# ESC.net
KiCad netlist of a schematic drawn in Altium Designer
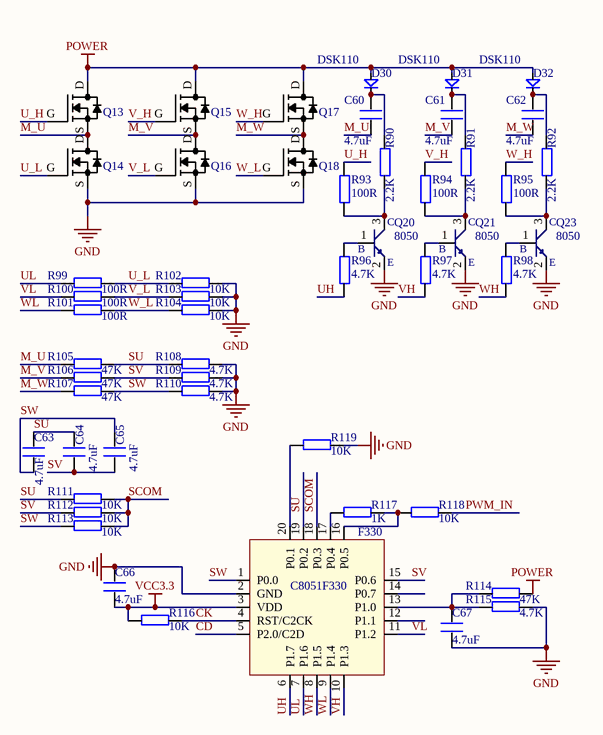
[diagram p0: ESC.SchDoc]

(export (version "E")
  (design (tool "Eeschema 10.0.6"))
  (components
    (comp (ref "C60")
      (value "4.7uF")
      (footprint "C 0603_L")
      (libsource (lib "WarShip V3 STM32103封装库") (part "C"))
    )
    (comp (ref "C61")
      (value "4.7uF")
      (footprint "C 0603_L")
      (libsource (lib "WarShip V3 STM32103封装库") (part "C"))
    )
    (comp (ref "C62")
      (value "4.7uF")
      (footprint "C 0603_L")
      (libsource (lib "WarShip V3 STM32103封装库") (part "C"))
    )
    (comp (ref "C63")
      (value "4.7uF")
      (footprint "C 0603_L")
      (libsource (lib "WarShip V3 STM32103封装库") (part "C"))
    )
    (comp (ref "C64")
      (value "4.7uF")
      (footprint "C 0603_L")
      (libsource (lib "WarShip V3 STM32103封装库") (part "C"))
    )
    (comp (ref "C65")
      (value "4.7uF")
      (footprint "C 0603_L")
      (libsource (lib "WarShip V3 STM32103封装库") (part "C"))
    )
    (comp (ref "C66")
      (value "4.7uF")
      (footprint "C 0603_L")
      (libsource (lib "WarShip V3 STM32103封装库") (part "C"))
    )
    (comp (ref "C67")
      (value "4.7uF")
      (footprint "C 0603_L")
      (libsource (lib "WarShip V3 STM32103封装库") (part "C"))
    )
    (comp (ref "D30")
      (value "DSK110")
      (footprint "SOD-123F")
      (description "通用二极管 100V-1A")
      (fields (field (name "版权归属") "源创客"))
      (libsource (lib "二极管-整流桥") (part "DSK110"))
    )
    (comp (ref "D31")
      (value "DSK110")
      (footprint "SOD-123F")
      (description "通用二极管 100V-1A")
      (fields (field (name "版权归属") "源创客"))
      (libsource (lib "二极管-整流桥") (part "DSK110"))
    )
    (comp (ref "D32")
      (value "DSK110")
      (footprint "SOD-123F")
      (description "通用二极管 100V-1A")
      (fields (field (name "版权归属") "源创客"))
      (libsource (lib "二极管-整流桥") (part "DSK110"))
    )
    (comp (ref "F330")
      (value "C8051F330")
      (footprint "QFN20_4*4_L")
      (description "C8051F330单片机")
      (libsource (lib "LovelessingSch") (part "C8051F330"))
    )
    (comp (ref "Q13")
      (value "NTMFS5C628NLT")
      (footprint "SO_8FL_DFN5")
      (description "MOSFET N-CH 60V SO8FL")
      (fields
        (field (name "MANUFACTURER") "ON Semiconductor")
        (field (name "MANUFACTURER PART NUMBER") "NTMFS5C628NLT1G")
      )
      (libsource (lib "MINIBLDC") (part "NTMFS5C628NLT"))
    )
    (comp (ref "Q14")
      (value "NTMFS5C628NLT")
      (footprint "SO_8FL_DFN5")
      (description "MOSFET N-CH 60V SO8FL")
      (fields
        (field (name "MANUFACTURER") "ON Semiconductor")
        (field (name "MANUFACTURER PART NUMBER") "NTMFS5C628NLT1G")
      )
      (libsource (lib "MINIBLDC") (part "NTMFS5C628NLT"))
    )
    (comp (ref "Q15")
      (value "NTMFS5C628NLT")
      (footprint "SO_8FL_DFN5")
      (description "MOSFET N-CH 60V SO8FL")
      (fields
        (field (name "MANUFACTURER") "ON Semiconductor")
        (field (name "MANUFACTURER PART NUMBER") "NTMFS5C628NLT1G")
      )
      (libsource (lib "MINIBLDC") (part "NTMFS5C628NLT"))
    )
    (comp (ref "Q16")
      (value "NTMFS5C628NLT")
      (footprint "SO_8FL_DFN5")
      (description "MOSFET N-CH 60V SO8FL")
      (fields
        (field (name "MANUFACTURER") "ON Semiconductor")
        (field (name "MANUFACTURER PART NUMBER") "NTMFS5C628NLT1G")
      )
      (libsource (lib "MINIBLDC") (part "NTMFS5C628NLT"))
    )
    (comp (ref "Q17")
      (value "NTMFS5C628NLT")
      (footprint "SO_8FL_DFN5")
      (description "MOSFET N-CH 60V SO8FL")
      (fields
        (field (name "MANUFACTURER") "ON Semiconductor")
        (field (name "MANUFACTURER PART NUMBER") "NTMFS5C628NLT1G")
      )
      (libsource (lib "MINIBLDC") (part "NTMFS5C628NLT"))
    )
    (comp (ref "Q18")
      (value "NTMFS5C628NLT")
      (footprint "SO_8FL_DFN5")
      (description "MOSFET N-CH 60V SO8FL")
      (fields
        (field (name "MANUFACTURER") "ON Semiconductor")
        (field (name "MANUFACTURER PART NUMBER") "NTMFS5C628NLT1G")
      )
      (libsource (lib "MINIBLDC") (part "NTMFS5C628NLT"))
    )
    (comp (ref "Q20")
      (value "8050")
      (footprint "SOT23-3L")
      (libsource (lib "LovelessingSch") (part "8050NPN"))
    )
    (comp (ref "Q21")
      (value "8050")
      (footprint "SOT23-3L")
      (libsource (lib "LovelessingSch") (part "8050NPN"))
    )
    (comp (ref "Q23")
      (value "8050")
      (footprint "SOT23-3L")
      (libsource (lib "LovelessingSch") (part "8050NPN"))
    )
    (comp (ref "R90")
      (value "2.2K")
      (footprint "R 0603_L")
      (libsource (lib "WarShip V3 STM32103封装库") (part "R"))
    )
    (comp (ref "R91")
      (value "2.2K")
      (footprint "R 0603_L")
      (libsource (lib "WarShip V3 STM32103封装库") (part "R"))
    )
    (comp (ref "R92")
      (value "2.2K")
      (footprint "R 0603_L")
      (libsource (lib "WarShip V3 STM32103封装库") (part "R"))
    )
    (comp (ref "R93")
      (value "100R")
      (footprint "R 0603_L")
      (libsource (lib "WarShip V3 STM32103封装库") (part "R"))
    )
    (comp (ref "R94")
      (value "100R")
      (footprint "R 0603_L")
      (libsource (lib "WarShip V3 STM32103封装库") (part "R"))
    )
    (comp (ref "R95")
      (value "100R")
      (footprint "R 0603_L")
      (libsource (lib "WarShip V3 STM32103封装库") (part "R"))
    )
    (comp (ref "R96")
      (value "4.7K")
      (footprint "R 0603_L")
      (libsource (lib "WarShip V3 STM32103封装库") (part "R"))
    )
    (comp (ref "R97")
      (value "4.7K")
      (footprint "R 0603_L")
      (libsource (lib "WarShip V3 STM32103封装库") (part "R"))
    )
    (comp (ref "R98")
      (value "4.7K")
      (footprint "R 0603_L")
      (libsource (lib "WarShip V3 STM32103封装库") (part "R"))
    )
    (comp (ref "R99")
      (value "100R")
      (footprint "R 0603_L")
      (libsource (lib "WarShip V3 STM32103封装库") (part "R"))
    )
    (comp (ref "R100")
      (value "100R")
      (footprint "R 0603_L")
      (libsource (lib "WarShip V3 STM32103封装库") (part "R"))
    )
    (comp (ref "R101")
      (value "100R")
      (footprint "R 0603_L")
      (libsource (lib "WarShip V3 STM32103封装库") (part "R"))
    )
    (comp (ref "R102")
      (value "10K")
      (footprint "R 0603_L")
      (libsource (lib "WarShip V3 STM32103封装库") (part "R"))
    )
    (comp (ref "R103")
      (value "10K")
      (footprint "R 0603_L")
      (libsource (lib "WarShip V3 STM32103封装库") (part "R"))
    )
    (comp (ref "R104")
      (value "10K")
      (footprint "R 0603_L")
      (libsource (lib "WarShip V3 STM32103封装库") (part "R"))
    )
    (comp (ref "R105")
      (value "47K")
      (footprint "R 0603_L")
      (libsource (lib "WarShip V3 STM32103封装库") (part "R"))
    )
    (comp (ref "R106")
      (value "47K")
      (footprint "R 0603_L")
      (libsource (lib "WarShip V3 STM32103封装库") (part "R"))
    )
    (comp (ref "R107")
      (value "47K")
      (footprint "R 0603_L")
      (libsource (lib "WarShip V3 STM32103封装库") (part "R"))
    )
    (comp (ref "R108")
      (value "4.7K")
      (footprint "R 0603_L")
      (libsource (lib "WarShip V3 STM32103封装库") (part "R"))
    )
    (comp (ref "R109")
      (value "4.7K")
      (footprint "R 0603_L")
      (libsource (lib "WarShip V3 STM32103封装库") (part "R"))
    )
    (comp (ref "R110")
      (value "4.7K")
      (footprint "R 0603_L")
      (libsource (lib "WarShip V3 STM32103封装库") (part "R"))
    )
    (comp (ref "R111")
      (value "10K")
      (footprint "R 0603_L")
      (libsource (lib "WarShip V3 STM32103封装库") (part "R"))
    )
    (comp (ref "R112")
      (value "10K")
      (footprint "R 0603_L")
      (libsource (lib "WarShip V3 STM32103封装库") (part "R"))
    )
    (comp (ref "R113")
      (value "10K")
      (footprint "R 0603_L")
      (libsource (lib "WarShip V3 STM32103封装库") (part "R"))
    )
    (comp (ref "R114")
      (value "47K")
      (footprint "R 0603_L")
      (libsource (lib "WarShip V3 STM32103封装库") (part "R"))
    )
    (comp (ref "R115")
      (value "4.7K")
      (footprint "R 0603_L")
      (libsource (lib "WarShip V3 STM32103封装库") (part "R"))
    )
    (comp (ref "R116")
      (value "10K")
      (footprint "R 0603_L")
      (libsource (lib "WarShip V3 STM32103封装库") (part "R"))
    )
    (comp (ref "R117")
      (value "1K")
      (footprint "R 0603_L")
      (libsource (lib "WarShip V3 STM32103封装库") (part "R"))
    )
    (comp (ref "R118")
      (value "10K")
      (footprint "R 0603_L")
      (libsource (lib "WarShip V3 STM32103封装库") (part "R"))
    )
    (comp (ref "R119")
      (value "10K")
      (footprint "R 0603_L")
      (libsource (lib "WarShip V3 STM32103封装库") (part "R"))
    )
  )
  (nets
    (net (code "1") (name "/CD") (class "Default")
      (node (ref "F330") (pin "5") (pinfunction "P2.0/C2D_5") (pintype "passive"))
    )
    (net (code "2") (name "/CK") (class "Default")
      (node (ref "F330") (pin "4") (pinfunction "RST/C2CK_4") (pintype "passive"))
      (node (ref "R116") (pin "1") (pintype "passive"))
    )
    (net (code "3") (name "/M_U") (class "Default")
      (node (ref "C60") (pin "1") (pintype "passive"))
      (node (ref "Q13") (pin "S") (pinfunction "S_S") (pintype "passive"))
      (node (ref "Q14") (pin "D") (pinfunction "D_D") (pintype "passive"))
      (node (ref "R105") (pin "2") (pintype "passive"))
    )
    (net (code "4") (name "/M_V") (class "Default")
      (node (ref "C61") (pin "1") (pintype "passive"))
      (node (ref "Q15") (pin "S") (pinfunction "S_S") (pintype "passive"))
      (node (ref "Q16") (pin "D") (pinfunction "D_D") (pintype "passive"))
      (node (ref "R106") (pin "2") (pintype "passive"))
    )
    (net (code "5") (name "/M_W") (class "Default")
      (node (ref "C62") (pin "1") (pintype "passive"))
      (node (ref "Q17") (pin "S") (pinfunction "S_S") (pintype "passive"))
      (node (ref "Q18") (pin "D") (pinfunction "D_D") (pintype "passive"))
      (node (ref "R107") (pin "2") (pintype "passive"))
    )
    (net (code "6") (name "/PWM_IN") (class "Default") (node (ref "R118") (pin "1") (pintype "passive")))
    (net (code "7") (name "/SCOM") (class "Default")
      (node (ref "F330") (pin "18") (pinfunction "P0.3_18") (pintype "passive"))
      (node (ref "R111") (pin "1") (pintype "passive"))
      (node (ref "R112") (pin "1") (pintype "passive"))
      (node (ref "R113") (pin "1") (pintype "passive"))
    )
    (net (code "8") (name "/SU") (class "Default")
      (node (ref "C63") (pin "2") (pintype "passive"))
      (node (ref "C64") (pin "2") (pintype "passive"))
      (node (ref "F330") (pin "19") (pinfunction "P0.2_19") (pintype "passive"))
      (node (ref "R105") (pin "1") (pintype "passive"))
      (node (ref "R108") (pin "2") (pintype "passive"))
      (node (ref "R111") (pin "2") (pintype "passive"))
    )
    (net (code "9") (name "/SV") (class "Default")
      (node (ref "C64") (pin "1") (pintype "passive"))
      (node (ref "C65") (pin "1") (pintype "passive"))
      (node (ref "F330") (pin "15") (pinfunction "P0.6_15") (pintype "passive"))
      (node (ref "R106") (pin "1") (pintype "passive"))
      (node (ref "R109") (pin "2") (pintype "passive"))
      (node (ref "R112") (pin "2") (pintype "passive"))
    )
    (net (code "10") (name "/SW") (class "Default")
      (node (ref "C63") (pin "1") (pintype "passive"))
      (node (ref "C65") (pin "2") (pintype "passive"))
      (node (ref "F330") (pin "1") (pinfunction "P0.0_1") (pintype "passive"))
      (node (ref "R107") (pin "1") (pintype "passive"))
      (node (ref "R110") (pin "2") (pintype "passive"))
      (node (ref "R113") (pin "2") (pintype "passive"))
    )
    (net (code "11") (name "/UH") (class "Default")
      (node (ref "F330") (pin "6") (pinfunction "P1.7_6") (pintype "passive"))
      (node (ref "R96") (pin "1") (pintype "passive"))
    )
    (net (code "12") (name "/UL") (class "Default")
      (node (ref "F330") (pin "7") (pinfunction "P1.6_7") (pintype "passive"))
      (node (ref "R99") (pin "2") (pintype "passive"))
    )
    (net (code "13") (name "/U_H") (class "Default")
      (node (ref "Q13") (pin "G") (pinfunction "G_G") (pintype "passive"))
      (node (ref "R93") (pin "2") (pintype "passive"))
    )
    (net (code "14") (name "/U_L") (class "Default")
      (node (ref "Q14") (pin "G") (pinfunction "G_G") (pintype "passive"))
      (node (ref "R102") (pin "2") (pintype "passive"))
      (node (ref "R99") (pin "1") (pintype "passive"))
    )
    (net (code "15") (name "/VH") (class "Default")
      (node (ref "F330") (pin "10") (pinfunction "P1.3_10") (pintype "passive"))
      (node (ref "R97") (pin "1") (pintype "passive"))
    )
    (net (code "16") (name "/VL") (class "Default")
      (node (ref "F330") (pin "11") (pinfunction "P1.2_11") (pintype "passive"))
      (node (ref "R100") (pin "2") (pintype "passive"))
    )
    (net (code "17") (name "/V_H") (class "Default")
      (node (ref "Q15") (pin "G") (pinfunction "G_G") (pintype "passive"))
      (node (ref "R94") (pin "2") (pintype "passive"))
    )
    (net (code "18") (name "/V_L") (class "Default")
      (node (ref "Q16") (pin "G") (pinfunction "G_G") (pintype "passive"))
      (node (ref "R100") (pin "1") (pintype "passive"))
      (node (ref "R103") (pin "2") (pintype "passive"))
    )
    (net (code "19") (name "/WH") (class "Default")
      (node (ref "F330") (pin "8") (pinfunction "P1.5_8") (pintype "passive"))
      (node (ref "R98") (pin "1") (pintype "passive"))
    )
    (net (code "20") (name "/WL") (class "Default")
      (node (ref "F330") (pin "9") (pinfunction "P1.4_9") (pintype "passive"))
      (node (ref "R101") (pin "2") (pintype "passive"))
    )
    (net (code "21") (name "/W_H") (class "Default")
      (node (ref "Q17") (pin "G") (pinfunction "G_G") (pintype "passive"))
      (node (ref "R95") (pin "2") (pintype "passive"))
    )
    (net (code "22") (name "/W_L") (class "Default")
      (node (ref "Q18") (pin "G") (pinfunction "G_G") (pintype "passive"))
      (node (ref "R101") (pin "1") (pintype "passive"))
      (node (ref "R104") (pin "2") (pintype "passive"))
    )
    (net (code "23") (name "GND") (class "Default")
      (node (ref "C66") (pin "1") (pintype "passive"))
      (node (ref "C67") (pin "2") (pintype "passive"))
      (node (ref "F330") (pin "2") (pinfunction "GND_2") (pintype "passive"))
      (node (ref "Q14") (pin "S") (pinfunction "S_S") (pintype "passive"))
      (node (ref "Q16") (pin "S") (pinfunction "S_S") (pintype "passive"))
      (node (ref "Q18") (pin "S") (pinfunction "S_S") (pintype "passive"))
      (node (ref "Q20") (pin "2") (pinfunction "E_2") (pintype "passive"))
      (node (ref "Q21") (pin "2") (pinfunction "E_2") (pintype "passive"))
      (node (ref "Q23") (pin "2") (pinfunction "E_2") (pintype "passive"))
      (node (ref "R102") (pin "1") (pintype "passive"))
      (node (ref "R103") (pin "1") (pintype "passive"))
      (node (ref "R104") (pin "1") (pintype "passive"))
      (node (ref "R108") (pin "1") (pintype "passive"))
      (node (ref "R109") (pin "1") (pintype "passive"))
      (node (ref "R110") (pin "1") (pintype "passive"))
      (node (ref "R115") (pin "1") (pintype "passive"))
      (node (ref "R119") (pin "1") (pintype "passive"))
    )
    (net (code "24") (name "Net-(D30-K)") (class "Default")
      (node (ref "C60") (pin "2") (pintype "passive"))
      (node (ref "D30") (pin "2") (pinfunction "K_2") (pintype "passive"))
      (node (ref "R90") (pin "2") (pintype "passive"))
    )
    (net (code "25") (name "Net-(D31-K)") (class "Default")
      (node (ref "C61") (pin "2") (pintype "passive"))
      (node (ref "D31") (pin "2") (pinfunction "K_2") (pintype "passive"))
      (node (ref "R91") (pin "2") (pintype "passive"))
    )
    (net (code "26") (name "Net-(D32-K)") (class "Default")
      (node (ref "C62") (pin "2") (pintype "passive"))
      (node (ref "D32") (pin "2") (pinfunction "K_2") (pintype "passive"))
      (node (ref "R92") (pin "2") (pintype "passive"))
    )
    (net (code "27") (name "Net-(F330-P0.1)") (class "Default")
      (node (ref "F330") (pin "20") (pinfunction "P0.1_20") (pintype "passive"))
      (node (ref "R119") (pin "2") (pintype "passive"))
    )
    (net (code "28") (name "Net-(F330-P0.4)") (class "Default")
      (node (ref "F330") (pin "17") (pinfunction "P0.4_17") (pintype "passive"))
      (node (ref "R117") (pin "2") (pintype "passive"))
    )
    (net (code "29") (name "Net-(F330-P0.5)") (class "Default")
      (node (ref "F330") (pin "16") (pinfunction "P0.5_16") (pintype "passive"))
      (node (ref "R117") (pin "1") (pintype "passive"))
      (node (ref "R118") (pin "2") (pintype "passive"))
    )
    (net (code "30") (name "Net-(F330-P1.0)") (class "Default")
      (node (ref "C67") (pin "1") (pintype "passive"))
      (node (ref "F330") (pin "13") (pinfunction "P1.0_13") (pintype "passive"))
      (node (ref "R114") (pin "2") (pintype "passive"))
      (node (ref "R115") (pin "2") (pintype "passive"))
    )
    (net (code "31") (name "Net-(Q20-B)") (class "Default")
      (node (ref "Q20") (pin "1") (pinfunction "B_1") (pintype "passive"))
      (node (ref "R96") (pin "2") (pintype "passive"))
    )
    (net (code "32") (name "Net-(Q20-C)") (class "Default")
      (node (ref "Q20") (pin "3") (pinfunction "C_3") (pintype "passive"))
      (node (ref "R90") (pin "1") (pintype "passive"))
      (node (ref "R93") (pin "1") (pintype "passive"))
    )
    (net (code "33") (name "Net-(Q21-B)") (class "Default")
      (node (ref "Q21") (pin "1") (pinfunction "B_1") (pintype "passive"))
      (node (ref "R97") (pin "2") (pintype "passive"))
    )
    (net (code "34") (name "Net-(Q21-C)") (class "Default")
      (node (ref "Q21") (pin "3") (pinfunction "C_3") (pintype "passive"))
      (node (ref "R91") (pin "1") (pintype "passive"))
      (node (ref "R94") (pin "1") (pintype "passive"))
    )
    (net (code "35") (name "Net-(Q23-B)") (class "Default")
      (node (ref "Q23") (pin "1") (pinfunction "B_1") (pintype "passive"))
      (node (ref "R98") (pin "2") (pintype "passive"))
    )
    (net (code "36") (name "Net-(Q23-C)") (class "Default")
      (node (ref "Q23") (pin "3") (pinfunction "C_3") (pintype "passive"))
      (node (ref "R92") (pin "1") (pintype "passive"))
      (node (ref "R95") (pin "1") (pintype "passive"))
    )
    (net (code "37") (name "POWER") (class "Default")
      (node (ref "D30") (pin "1") (pinfunction "A_1") (pintype "passive"))
      (node (ref "D31") (pin "1") (pinfunction "A_1") (pintype "passive"))
      (node (ref "D32") (pin "1") (pinfunction "A_1") (pintype "passive"))
      (node (ref "Q13") (pin "D") (pinfunction "D_D") (pintype "passive"))
      (node (ref "Q15") (pin "D") (pinfunction "D_D") (pintype "passive"))
      (node (ref "Q17") (pin "D") (pinfunction "D_D") (pintype "passive"))
      (node (ref "R114") (pin "1") (pintype "passive"))
    )
    (net (code "38") (name "VCC3.3") (class "Default")
      (node (ref "C66") (pin "2") (pintype "passive"))
      (node (ref "F330") (pin "3") (pinfunction "VDD_3") (pintype "passive"))
      (node (ref "R116") (pin "2") (pintype "passive"))
    )
    (net (code "39") (name "unconnected-(F330-P0.7-Pad14)") (class "Default")
      (node (ref "F330") (pin "14") (pinfunction "P0.7_14") (pintype "passive"))
    )
    (net (code "40") (name "unconnected-(F330-P1.1-Pad12)") (class "Default")
      (node (ref "F330") (pin "12") (pinfunction "P1.1_12") (pintype "passive"))
    )
  )
)
